# emitter_follower_punto_di_lavoro.net
KiCad netlist of a schematic drawn in EAGLE
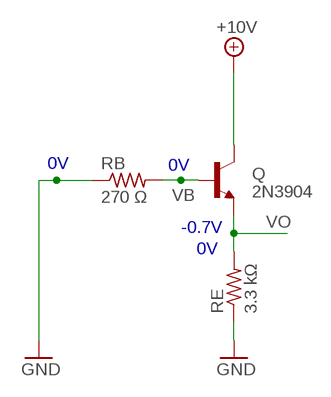
[diagram p0: schematic, sheet 1]

(export (version "E")
  (design (tool "Eeschema 10.0.6"))
  (components
    (comp (ref "Q")
      (value "2N3904")
      (footprint "eagle-import:TO92")
      (libsource (lib "eagle-import") (part "2N3904"))
    )
    (comp (ref "RB")
      (value "270 Ω")
      (footprint "eagle-import:0204_5")
      (libsource (lib "eagle-import") (part "R-US_0204/5"))
    )
    (comp (ref "RE")
      (value "3.3 kΩ")
      (footprint "eagle-import:0204_5")
      (libsource (lib "eagle-import") (part "R-US_0204/5"))
    )
  )
  (nets
    (net (code "1") (name "+10V") (class "Default")
      (node (ref "Q") (pin "1") (pinfunction "C_1") (pintype "passive"))
    )
    (net (code "2") (name "/VO") (class "Default")
      (node (ref "Q") (pin "3") (pinfunction "E_3") (pintype "passive"))
      (node (ref "RE") (pin "2") (pinfunction "2_2") (pintype "passive"))
    )
    (net (code "3") (name "GND") (class "Default")
      (node (ref "RB") (pin "1") (pinfunction "1_1") (pintype "passive"))
      (node (ref "RE") (pin "1") (pinfunction "1_1") (pintype "passive"))
    )
    (net (code "4") (name "Net-(Q-B)") (class "Default")
      (node (ref "Q") (pin "2") (pinfunction "B_2") (pintype "passive"))
      (node (ref "RB") (pin "2") (pinfunction "2_2") (pintype "passive"))
    )
  )
)
